# nixie-clock.net
KiCad netlist of a schematic drawn in EAGLE
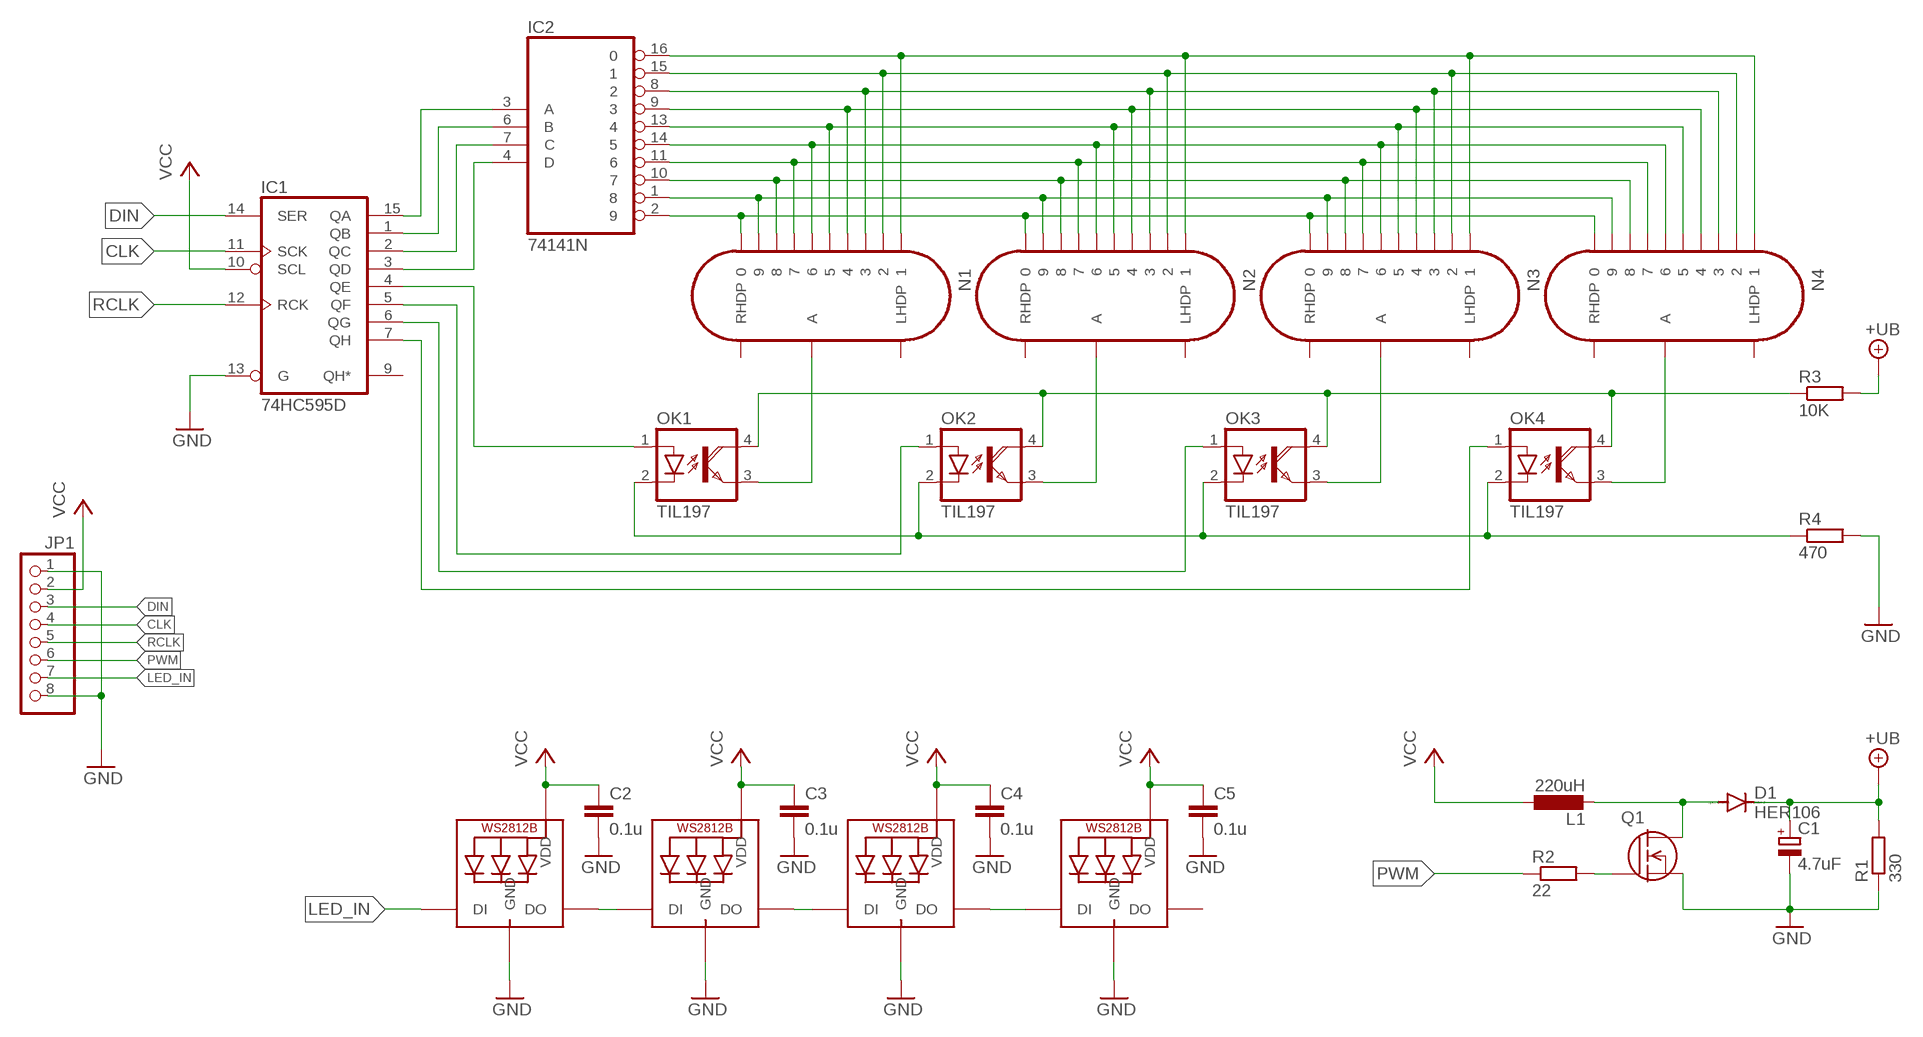
[diagram p0: schematic, sheet 1]

(export (version "E")
  (design (tool "Eeschema 10.0.6"))
  (components
    (comp (ref "C1")
      (value "4.7uF")
      (footprint "eagle-import:E3,5-8")
      (libsource (lib "eagle-import") (part "CPOL-EUE3.5-8"))
    )
    (comp (ref "C2")
      (value "0.1u")
      (footprint "eagle-import:C0805")
      (libsource (lib "eagle-import") (part "C-EUC0805"))
    )
    (comp (ref "C3")
      (value "0.1u")
      (footprint "eagle-import:C0805")
      (libsource (lib "eagle-import") (part "C-EUC0805"))
    )
    (comp (ref "C4")
      (value "0.1u")
      (footprint "eagle-import:C0805")
      (libsource (lib "eagle-import") (part "C-EUC0805"))
    )
    (comp (ref "C5")
      (value "0.1u")
      (footprint "eagle-import:C0805")
      (libsource (lib "eagle-import") (part "C-EUC0805"))
    )
    (comp (ref "D1")
      (value "HER106")
      (footprint "eagle-import:DO15-12")
      (libsource (lib "eagle-import") (part "DIODE-DO15-12"))
    )
    (comp (ref "IC1")
      (value "74HC595D")
      (footprint "eagle-import:SO16")
      (libsource (lib "eagle-import") (part "74595DHC"))
    )
    (comp (ref "IC2")
      (value "74141N")
      (footprint "eagle-import:DIL16")
      (libsource (lib "eagle-import") (part "74141N"))
    )
    (comp (ref "JP1")
      (value "PINHD-1X8")
      (footprint "eagle-import:1X08")
      (libsource (lib "eagle-import") (part "PINHD-1X8"))
    )
    (comp (ref "L1")
      (value "220uH")
      (footprint "eagle-import:6000-XXXX-RC")
      (libsource (lib "eagle-import") (part "L-EU6000-XXX-RC"))
    )
    (comp (ref "LED1")
      (value "WS2812B_5050N")
      (footprint "eagle-import:WS2812B-NARROW")
      (fields (field (name "MF") "Worldsemi") (field (name "MP") "WS2812B"))
      (libsource (lib "eagle-import") (part "WS2812B_5050N"))
    )
    (comp (ref "LED2")
      (value "WS2812B_5050N")
      (footprint "eagle-import:WS2812B-NARROW")
      (fields (field (name "MF") "Worldsemi") (field (name "MP") "WS2812B"))
      (libsource (lib "eagle-import") (part "WS2812B_5050N"))
    )
    (comp (ref "LED3")
      (value "WS2812B_5050N")
      (footprint "eagle-import:WS2812B-NARROW")
      (fields (field (name "MF") "Worldsemi") (field (name "MP") "WS2812B"))
      (libsource (lib "eagle-import") (part "WS2812B_5050N"))
    )
    (comp (ref "LED4")
      (value "WS2812B_5050N")
      (footprint "eagle-import:WS2812B-NARROW")
      (fields (field (name "MF") "Worldsemi") (field (name "MP") "WS2812B"))
      (libsource (lib "eagle-import") (part "WS2812B_5050N"))
    )
    (comp (ref "N1")
      (value "IN-14")
      (footprint "eagle-import:IN-14")
      (libsource (lib "eagle-import") (part "IN-14"))
    )
    (comp (ref "N2")
      (value "IN-14")
      (footprint "eagle-import:IN-14")
      (libsource (lib "eagle-import") (part "IN-14"))
    )
    (comp (ref "N3")
      (value "IN-14")
      (footprint "eagle-import:IN-14")
      (libsource (lib "eagle-import") (part "IN-14"))
    )
    (comp (ref "N4")
      (value "IN-14")
      (footprint "eagle-import:IN-14")
      (libsource (lib "eagle-import") (part "IN-14"))
    )
    (comp (ref "OK1")
      (value "TIL197")
      (footprint "eagle-import:DIL04")
      (libsource (lib "eagle-import") (part "TIL197"))
    )
    (comp (ref "OK2")
      (value "TIL197")
      (footprint "eagle-import:DIL04")
      (libsource (lib "eagle-import") (part "TIL197"))
    )
    (comp (ref "OK3")
      (value "TIL197")
      (footprint "eagle-import:DIL04")
      (libsource (lib "eagle-import") (part "TIL197"))
    )
    (comp (ref "OK4")
      (value "TIL197")
      (footprint "eagle-import:DIL04")
      (libsource (lib "eagle-import") (part "TIL197"))
    )
    (comp (ref "Q1")
      (value "IRF840")
      (footprint "eagle-import:TO220")
      (fields (field (name "MF") "Vishay Siliconix"))
      (libsource (lib "eagle-import") (part "IRF840"))
    )
    (comp (ref "R1")
      (value "330")
      (footprint "eagle-import:0207_7")
      (libsource (lib "eagle-import") (part "R-EU_0207/7"))
    )
    (comp (ref "R2")
      (value "22")
      (footprint "eagle-import:0207_7")
      (libsource (lib "eagle-import") (part "R-EU_0207/7"))
    )
    (comp (ref "R3")
      (value "10K")
      (footprint "eagle-import:0207_7")
      (libsource (lib "eagle-import") (part "R-EU_0207/7"))
    )
    (comp (ref "R4")
      (value "470")
      (footprint "eagle-import:0207_7")
      (libsource (lib "eagle-import") (part "R-EU_0207/7"))
    )
  )
  (nets
    (net (code "1") (name "+UB") (class "Default")
      (node (ref "C1") (pin "+") (pinfunction "+_+") (pintype "passive"))
      (node (ref "D1") (pin "C") (pinfunction "C_C") (pintype "passive"))
      (node (ref "R1") (pin "2") (pinfunction "2_2") (pintype "passive"))
      (node (ref "R3") (pin "2") (pinfunction "2_2") (pintype "passive"))
    )
    (net (code "2") (name "CLK") (class "Default")
      (node (ref "IC1") (pin "11") (pinfunction "SCK_11") (pintype "input"))
      (node (ref "JP1") (pin "4") (pinfunction "4_4") (pintype "passive"))
    )
    (net (code "3") (name "DIN") (class "Default")
      (node (ref "IC1") (pin "14") (pinfunction "SER_14") (pintype "input"))
      (node (ref "JP1") (pin "3") (pinfunction "3_3") (pintype "passive"))
    )
    (net (code "4") (name "GND") (class "Default")
      (node (ref "C1") (pin "-") (pinfunction "-_-") (pintype "passive"))
      (node (ref "C2") (pin "2") (pinfunction "2_2") (pintype "passive"))
      (node (ref "C3") (pin "2") (pinfunction "2_2") (pintype "passive"))
      (node (ref "C4") (pin "2") (pinfunction "2_2") (pintype "passive"))
      (node (ref "C5") (pin "2") (pinfunction "2_2") (pintype "passive"))
      (node (ref "IC1") (pin "13") (pinfunction "G_13") (pintype "input"))
      (node (ref "JP1") (pin "1") (pinfunction "1_1") (pintype "passive"))
      (node (ref "JP1") (pin "8") (pinfunction "8_8") (pintype "passive"))
      (node (ref "LED1") (pin "3-GND") (pinfunction "GND_3-GND") (pintype "power_in"))
      (node (ref "LED2") (pin "3-GND") (pinfunction "GND_3-GND") (pintype "power_in"))
      (node (ref "LED3") (pin "3-GND") (pinfunction "GND_3-GND") (pintype "power_in"))
      (node (ref "LED4") (pin "3-GND") (pinfunction "GND_3-GND") (pintype "power_in"))
      (node (ref "Q1") (pin "3") (pinfunction "S_3") (pintype "passive"))
      (node (ref "R1") (pin "1") (pinfunction "1_1") (pintype "passive"))
      (node (ref "R4") (pin "2") (pinfunction "2_2") (pintype "passive"))
    )
    (net (code "5") (name "LED_IN") (class "Default")
      (node (ref "JP1") (pin "7") (pinfunction "7_7") (pintype "passive"))
      (node (ref "LED1") (pin "4-DIN") (pinfunction "DI_4-DIN") (pintype "input"))
    )
    (net (code "6") (name "Net-(IC1A-QA)") (class "Default")
      (node (ref "IC1") (pin "15") (pinfunction "QA_15") (pintype "tri_state"))
      (node (ref "IC2") (pin "3") (pinfunction "A_3") (pintype "input"))
    )
    (net (code "7") (name "Net-(IC1A-QB)") (class "Default")
      (node (ref "IC1") (pin "1") (pinfunction "QB_1") (pintype "tri_state"))
      (node (ref "IC2") (pin "6") (pinfunction "B_6") (pintype "input"))
    )
    (net (code "8") (name "Net-(IC1A-QC)") (class "Default")
      (node (ref "IC1") (pin "2") (pinfunction "QC_2") (pintype "tri_state"))
      (node (ref "IC2") (pin "7") (pinfunction "C_7") (pintype "input"))
    )
    (net (code "9") (name "Net-(IC1A-QD)") (class "Default")
      (node (ref "IC1") (pin "3") (pinfunction "QD_3") (pintype "tri_state"))
      (node (ref "IC2") (pin "4") (pinfunction "D_4") (pintype "input"))
    )
    (net (code "10") (name "Net-(IC1A-QE)") (class "Default")
      (node (ref "IC1") (pin "4") (pinfunction "QE_4") (pintype "tri_state"))
      (node (ref "OK1") (pin "1") (pinfunction "A_1") (pintype "passive"))
    )
    (net (code "11") (name "Net-(IC1A-QF)") (class "Default")
      (node (ref "IC1") (pin "5") (pinfunction "QF_5") (pintype "tri_state"))
      (node (ref "OK2") (pin "1") (pinfunction "A_1") (pintype "passive"))
    )
    (net (code "12") (name "Net-(IC1A-QG)") (class "Default")
      (node (ref "IC1") (pin "6") (pinfunction "QG_6") (pintype "tri_state"))
      (node (ref "OK3") (pin "1") (pinfunction "A_1") (pintype "passive"))
    )
    (net (code "13") (name "Net-(IC1A-QH)") (class "Default")
      (node (ref "IC1") (pin "7") (pinfunction "QH_7") (pintype "tri_state"))
      (node (ref "OK4") (pin "1") (pinfunction "A_1") (pintype "passive"))
    )
    (net (code "14") (name "Net-(IC2A-0)") (class "Default")
      (node (ref "IC2") (pin "16") (pinfunction "0_16") (pintype "open_collector"))
      (node (ref "N1") (pin "1") (pinfunction "1_1") (pintype "bidirectional"))
      (node (ref "N2") (pin "1") (pinfunction "1_1") (pintype "bidirectional"))
      (node (ref "N3") (pin "1") (pinfunction "1_1") (pintype "bidirectional"))
      (node (ref "N4") (pin "1") (pinfunction "1_1") (pintype "bidirectional"))
    )
    (net (code "15") (name "Net-(IC2A-1)") (class "Default")
      (node (ref "IC2") (pin "15") (pinfunction "1_15") (pintype "open_collector"))
      (node (ref "N1") (pin "2") (pinfunction "2_2") (pintype "bidirectional"))
      (node (ref "N2") (pin "2") (pinfunction "2_2") (pintype "bidirectional"))
      (node (ref "N3") (pin "2") (pinfunction "2_2") (pintype "bidirectional"))
      (node (ref "N4") (pin "2") (pinfunction "2_2") (pintype "bidirectional"))
    )
    (net (code "16") (name "Net-(IC2A-2)") (class "Default")
      (node (ref "IC2") (pin "8") (pinfunction "2_8") (pintype "open_collector"))
      (node (ref "N1") (pin "3") (pinfunction "3_3") (pintype "bidirectional"))
      (node (ref "N2") (pin "3") (pinfunction "3_3") (pintype "bidirectional"))
      (node (ref "N3") (pin "3") (pinfunction "3_3") (pintype "bidirectional"))
      (node (ref "N4") (pin "3") (pinfunction "3_3") (pintype "bidirectional"))
    )
    (net (code "17") (name "Net-(IC2A-3)") (class "Default")
      (node (ref "IC2") (pin "9") (pinfunction "3_9") (pintype "open_collector"))
      (node (ref "N1") (pin "4") (pinfunction "4_4") (pintype "bidirectional"))
      (node (ref "N2") (pin "4") (pinfunction "4_4") (pintype "bidirectional"))
      (node (ref "N3") (pin "4") (pinfunction "4_4") (pintype "bidirectional"))
      (node (ref "N4") (pin "4") (pinfunction "4_4") (pintype "bidirectional"))
    )
    (net (code "18") (name "Net-(IC2A-4)") (class "Default")
      (node (ref "IC2") (pin "13") (pinfunction "4_13") (pintype "open_collector"))
      (node (ref "N1") (pin "5") (pinfunction "5_5") (pintype "bidirectional"))
      (node (ref "N2") (pin "5") (pinfunction "5_5") (pintype "bidirectional"))
      (node (ref "N3") (pin "5") (pinfunction "5_5") (pintype "bidirectional"))
      (node (ref "N4") (pin "5") (pinfunction "5_5") (pintype "bidirectional"))
    )
    (net (code "19") (name "Net-(IC2A-5)") (class "Default")
      (node (ref "IC2") (pin "14") (pinfunction "5_14") (pintype "open_collector"))
      (node (ref "N1") (pin "6") (pinfunction "6_6") (pintype "bidirectional"))
      (node (ref "N2") (pin "6") (pinfunction "6_6") (pintype "bidirectional"))
      (node (ref "N3") (pin "6") (pinfunction "6_6") (pintype "bidirectional"))
      (node (ref "N4") (pin "6") (pinfunction "6_6") (pintype "bidirectional"))
    )
    (net (code "20") (name "Net-(IC2A-6)") (class "Default")
      (node (ref "IC2") (pin "11") (pinfunction "6_11") (pintype "open_collector"))
      (node (ref "N1") (pin "7") (pinfunction "7_7") (pintype "bidirectional"))
      (node (ref "N2") (pin "7") (pinfunction "7_7") (pintype "bidirectional"))
      (node (ref "N3") (pin "7") (pinfunction "7_7") (pintype "bidirectional"))
      (node (ref "N4") (pin "7") (pinfunction "7_7") (pintype "bidirectional"))
    )
    (net (code "21") (name "Net-(IC2A-7)") (class "Default")
      (node (ref "IC2") (pin "10") (pinfunction "7_10") (pintype "open_collector"))
      (node (ref "N1") (pin "8") (pinfunction "8_8") (pintype "bidirectional"))
      (node (ref "N2") (pin "8") (pinfunction "8_8") (pintype "bidirectional"))
      (node (ref "N3") (pin "8") (pinfunction "8_8") (pintype "bidirectional"))
      (node (ref "N4") (pin "8") (pinfunction "8_8") (pintype "bidirectional"))
    )
    (net (code "22") (name "Net-(IC2A-8)") (class "Default")
      (node (ref "IC2") (pin "1") (pinfunction "8_1") (pintype "open_collector"))
      (node (ref "N1") (pin "9") (pinfunction "9_9") (pintype "bidirectional"))
      (node (ref "N2") (pin "9") (pinfunction "9_9") (pintype "bidirectional"))
      (node (ref "N3") (pin "9") (pinfunction "9_9") (pintype "bidirectional"))
      (node (ref "N4") (pin "9") (pinfunction "9_9") (pintype "bidirectional"))
    )
    (net (code "23") (name "Net-(IC2A-9)") (class "Default")
      (node (ref "IC2") (pin "2") (pinfunction "9_2") (pintype "open_collector"))
      (node (ref "N1") (pin "0") (pinfunction "0_0") (pintype "bidirectional"))
      (node (ref "N2") (pin "0") (pinfunction "0_0") (pintype "bidirectional"))
      (node (ref "N3") (pin "0") (pinfunction "0_0") (pintype "bidirectional"))
      (node (ref "N4") (pin "0") (pinfunction "0_0") (pintype "bidirectional"))
    )
    (net (code "24") (name "Net-(LED1-DO)") (class "Default")
      (node (ref "LED1") (pin "2-DOUT") (pinfunction "DO_2-DOUT") (pintype "output"))
      (node (ref "LED2") (pin "4-DIN") (pinfunction "DI_4-DIN") (pintype "input"))
    )
    (net (code "25") (name "Net-(LED2-DO)") (class "Default")
      (node (ref "LED2") (pin "2-DOUT") (pinfunction "DO_2-DOUT") (pintype "output"))
      (node (ref "LED3") (pin "4-DIN") (pinfunction "DI_4-DIN") (pintype "input"))
    )
    (net (code "26") (name "Net-(LED3-DO)") (class "Default")
      (node (ref "LED3") (pin "2-DOUT") (pinfunction "DO_2-DOUT") (pintype "output"))
      (node (ref "LED4") (pin "4-DIN") (pinfunction "DI_4-DIN") (pintype "input"))
    )
    (net (code "27") (name "Net-(OK1-C)") (class "Default")
      (node (ref "OK1") (pin "2") (pinfunction "C_2") (pintype "passive"))
      (node (ref "OK2") (pin "2") (pinfunction "C_2") (pintype "passive"))
      (node (ref "OK3") (pin "2") (pinfunction "C_2") (pintype "passive"))
      (node (ref "OK4") (pin "2") (pinfunction "C_2") (pintype "passive"))
      (node (ref "R4") (pin "1") (pinfunction "1_1") (pintype "passive"))
    )
    (net (code "28") (name "Net-(OK1-COL)") (class "Default")
      (node (ref "OK1") (pin "4") (pinfunction "COL_4") (pintype "passive"))
      (node (ref "OK2") (pin "4") (pinfunction "COL_4") (pintype "passive"))
      (node (ref "OK3") (pin "4") (pinfunction "COL_4") (pintype "passive"))
      (node (ref "OK4") (pin "4") (pinfunction "COL_4") (pintype "passive"))
      (node (ref "R3") (pin "1") (pinfunction "1_1") (pintype "passive"))
    )
    (net (code "29") (name "Net-(OK1-EMI)") (class "Default")
      (node (ref "N1") (pin "A") (pinfunction "A_A") (pintype "bidirectional"))
      (node (ref "OK1") (pin "3") (pinfunction "EMI_3") (pintype "passive"))
    )
    (net (code "30") (name "Net-(OK2-EMI)") (class "Default")
      (node (ref "N2") (pin "A") (pinfunction "A_A") (pintype "bidirectional"))
      (node (ref "OK2") (pin "3") (pinfunction "EMI_3") (pintype "passive"))
    )
    (net (code "31") (name "Net-(OK3-EMI)") (class "Default")
      (node (ref "N3") (pin "A") (pinfunction "A_A") (pintype "bidirectional"))
      (node (ref "OK3") (pin "3") (pinfunction "EMI_3") (pintype "passive"))
    )
    (net (code "32") (name "Net-(OK4-EMI)") (class "Default")
      (node (ref "N4") (pin "A") (pinfunction "A_A") (pintype "bidirectional"))
      (node (ref "OK4") (pin "3") (pinfunction "EMI_3") (pintype "passive"))
    )
    (net (code "33") (name "Net-(Q1-D)") (class "Default")
      (node (ref "D1") (pin "A") (pinfunction "A_A") (pintype "passive"))
      (node (ref "L1") (pin "2") (pinfunction "2_2") (pintype "passive"))
      (node (ref "Q1") (pin "2") (pinfunction "D_2") (pintype "passive"))
    )
    (net (code "34") (name "Net-(Q1-G)") (class "Default")
      (node (ref "Q1") (pin "1") (pinfunction "G_1") (pintype "passive"))
      (node (ref "R2") (pin "2") (pinfunction "2_2") (pintype "passive"))
    )
    (net (code "35") (name "PWM") (class "Default")
      (node (ref "JP1") (pin "6") (pinfunction "6_6") (pintype "passive"))
      (node (ref "R2") (pin "1") (pinfunction "1_1") (pintype "passive"))
    )
    (net (code "36") (name "RCLK") (class "Default")
      (node (ref "IC1") (pin "12") (pinfunction "RCK_12") (pintype "input"))
      (node (ref "JP1") (pin "5") (pinfunction "5_5") (pintype "passive"))
    )
    (net (code "37") (name "VCC") (class "Default")
      (node (ref "C2") (pin "1") (pinfunction "1_1") (pintype "passive"))
      (node (ref "C3") (pin "1") (pinfunction "1_1") (pintype "passive"))
      (node (ref "C4") (pin "1") (pinfunction "1_1") (pintype "passive"))
      (node (ref "C5") (pin "1") (pinfunction "1_1") (pintype "passive"))
      (node (ref "IC1") (pin "10") (pinfunction "SCL_10") (pintype "input"))
      (node (ref "JP1") (pin "2") (pinfunction "2_2") (pintype "passive"))
      (node (ref "L1") (pin "1") (pinfunction "1_1") (pintype "passive"))
      (node (ref "LED1") (pin "1-VDD") (pinfunction "VDD_1-VDD") (pintype "power_in"))
      (node (ref "LED2") (pin "1-VDD") (pinfunction "VDD_1-VDD") (pintype "power_in"))
      (node (ref "LED3") (pin "1-VDD") (pinfunction "VDD_1-VDD") (pintype "power_in"))
      (node (ref "LED4") (pin "1-VDD") (pinfunction "VDD_1-VDD") (pintype "power_in"))
    )
    (net (code "38") (name "unconnected-(IC1A-QH*-Pad9)") (class "Default")
      (node (ref "IC1") (pin "9") (pinfunction "QH*_9") (pintype "tri_state"))
    )
    (net (code "39") (name "unconnected-(LED4-DO-Pad2-DOUT)") (class "Default")
      (node (ref "LED4") (pin "2-DOUT") (pinfunction "DO_2-DOUT") (pintype "output"))
    )
    (net (code "40") (name "unconnected-(N1-PadLHDP)") (class "Default")
      (node (ref "N1") (pin "LHDP") (pinfunction "LHDP_LHDP") (pintype "bidirectional"))
    )
    (net (code "41") (name "unconnected-(N1-PadRHDP)") (class "Default")
      (node (ref "N1") (pin "RHDP") (pinfunction "RHDP_RHDP") (pintype "bidirectional"))
    )
    (net (code "42") (name "unconnected-(N2-PadLHDP)") (class "Default")
      (node (ref "N2") (pin "LHDP") (pinfunction "LHDP_LHDP") (pintype "bidirectional"))
    )
    (net (code "43") (name "unconnected-(N2-PadRHDP)") (class "Default")
      (node (ref "N2") (pin "RHDP") (pinfunction "RHDP_RHDP") (pintype "bidirectional"))
    )
    (net (code "44") (name "unconnected-(N3-PadLHDP)") (class "Default")
      (node (ref "N3") (pin "LHDP") (pinfunction "LHDP_LHDP") (pintype "bidirectional"))
    )
    (net (code "45") (name "unconnected-(N3-PadRHDP)") (class "Default")
      (node (ref "N3") (pin "RHDP") (pinfunction "RHDP_RHDP") (pintype "bidirectional"))
    )
    (net (code "46") (name "unconnected-(N4-PadLHDP)") (class "Default")
      (node (ref "N4") (pin "LHDP") (pinfunction "LHDP_LHDP") (pintype "bidirectional"))
    )
    (net (code "47") (name "unconnected-(N4-PadRHDP)") (class "Default")
      (node (ref "N4") (pin "RHDP") (pinfunction "RHDP_RHDP") (pintype "bidirectional"))
    )
  )
)
